# companion.net
KiCad netlist of a schematic drawn in EAGLE
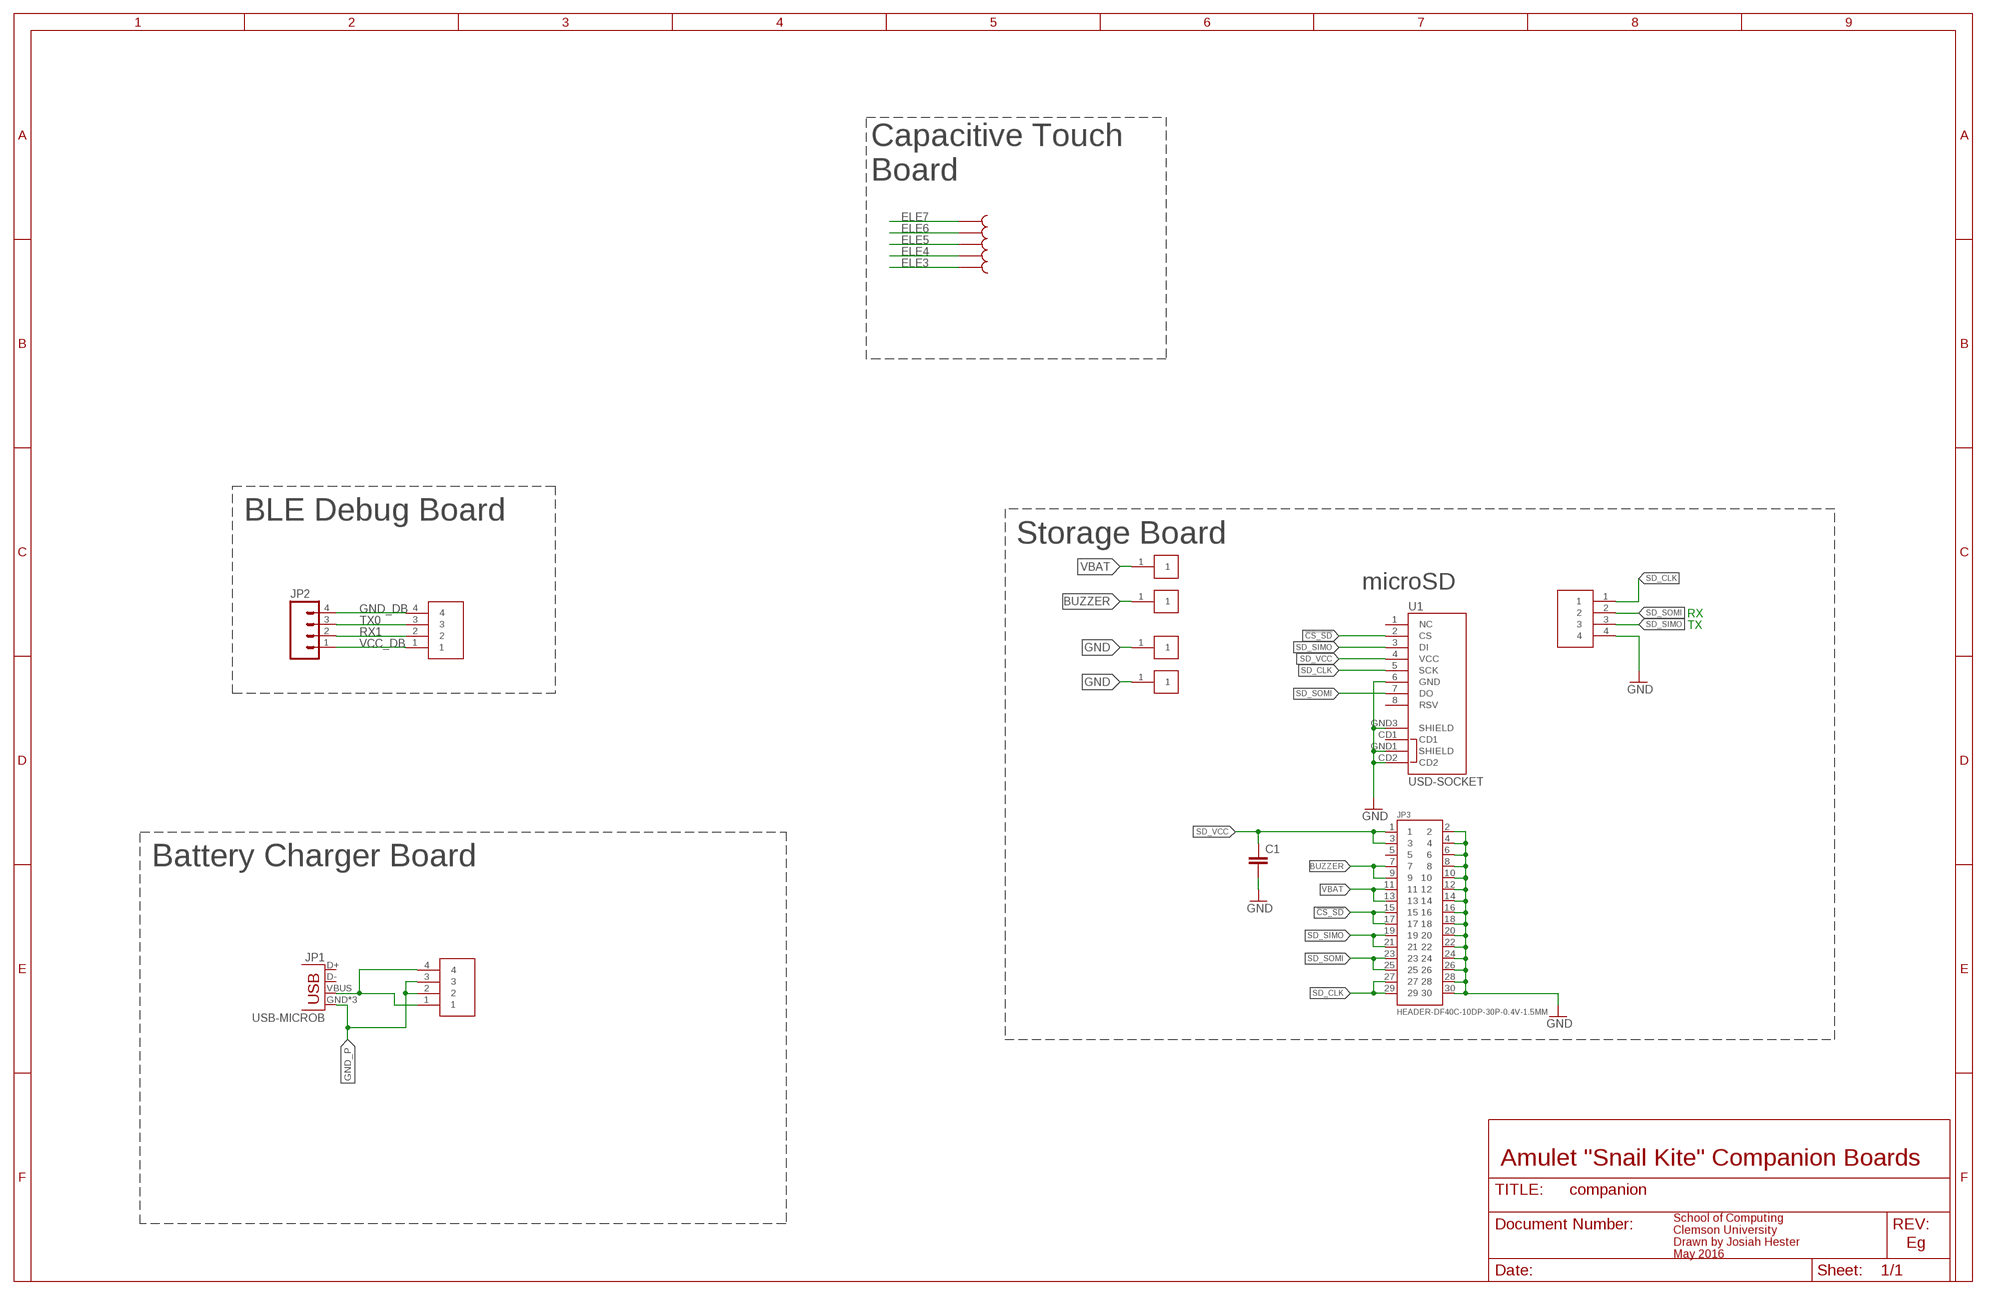
[diagram p0: schematic, sheet 1]

(export (version "E")
  (design (tool "Eeschema 10.0.6"))
  (components
    (comp (ref "C1")
      (value "CAP0805")
      (footprint "eagle-import:0805")
      (libsource (lib "eagle-import") (part "CAP0805"))
    )
    (comp (ref "JP1")
      (value "USB-MICROB")
      (footprint "eagle-import:USB-MICROB")
      (libsource (lib "eagle-import") (part "USB-MICROB"))
    )
    (comp (ref "JP2")
      (value "M04LOCK")
      (footprint "eagle-import:1X04_LOCK")
      (libsource (lib "eagle-import") (part "M04LOCK"))
    )
    (comp (ref "JP3")
      (value "HEADER-DF40C-10DP-30P-0.4V-1.5MM")
      (footprint "eagle-import:HEADER-DF40-30")
      (fields (field (name "DIGIKEY") "H11622CT-ND "))
      (libsource (lib "eagle-import") (part "HEADER-DF40C-10DP-30P-0.4V-1.5MM"))
    )
    (comp (ref "U$1")
      (value "CTPAD")
      (footprint "eagle-import:CTPAD")
      (libsource (lib "eagle-import") (part "CTPAD"))
    )
    (comp (ref "U$2")
      (value "CTPAD")
      (footprint "eagle-import:CTPAD")
      (libsource (lib "eagle-import") (part "CTPAD"))
    )
    (comp (ref "U$3")
      (value "CTPAD")
      (footprint "eagle-import:CTPAD")
      (libsource (lib "eagle-import") (part "CTPAD"))
    )
    (comp (ref "U$4")
      (value "CTPAD")
      (footprint "eagle-import:CTPAD")
      (libsource (lib "eagle-import") (part "CTPAD"))
    )
    (comp (ref "U$5")
      (value "CTPAD")
      (footprint "eagle-import:CTPAD")
      (libsource (lib "eagle-import") (part "CTPAD"))
    )
    (comp (ref "U$6")
      (value "1PAD")
      (footprint "eagle-import:5X23MM_PAD")
      (libsource (lib "eagle-import") (part "1PAD"))
    )
    (comp (ref "U$7")
      (value "1PAD")
      (footprint "eagle-import:5X23MM_PAD")
      (libsource (lib "eagle-import") (part "1PAD"))
    )
    (comp (ref "U$8")
      (value "1PAD")
      (footprint "eagle-import:5X23MM_PAD")
      (libsource (lib "eagle-import") (part "1PAD"))
    )
    (comp (ref "U$9")
      (value "1PAD")
      (footprint "eagle-import:5X23MM_PAD")
      (libsource (lib "eagle-import") (part "1PAD"))
    )
    (comp (ref "U$10")
      (value "1.27MM-MILLMAX")
      (footprint "eagle-import:1X03-1.27MM")
      (libsource (lib "eagle-import") (part "1.27MM-MILLMAX"))
    )
    (comp (ref "U$11")
      (value "1.27MM-MILLMAX")
      (footprint "eagle-import:1X03-1.27MM")
      (libsource (lib "eagle-import") (part "1.27MM-MILLMAX"))
    )
    (comp (ref "U$12")
      (value "1.27MM-MILLMAX")
      (footprint "eagle-import:1X03-1.27MM")
      (libsource (lib "eagle-import") (part "1.27MM-MILLMAX"))
    )
    (comp (ref "U1")
      (value "USD-SOCKET")
      (footprint "eagle-import:MICROSD_1_1")
      (libsource (lib "eagle-import") (part "USD-SOCKET"))
    )
  )
  (nets
    (net (code "1") (name "/ELE3") (class "Default")
      (node (ref "U$5") (pin "P$1") (pinfunction "P$1_P$1") (pintype "bidirectional"))
    )
    (net (code "2") (name "/ELE4") (class "Default")
      (node (ref "U$4") (pin "P$1") (pinfunction "P$1_P$1") (pintype "bidirectional"))
    )
    (net (code "3") (name "/ELE5") (class "Default")
      (node (ref "U$3") (pin "P$1") (pinfunction "P$1_P$1") (pintype "bidirectional"))
    )
    (net (code "4") (name "/ELE6") (class "Default")
      (node (ref "U$2") (pin "P$1") (pinfunction "P$1_P$1") (pintype "bidirectional"))
    )
    (net (code "5") (name "/ELE7") (class "Default")
      (node (ref "U$1") (pin "P$1") (pinfunction "P$1_P$1") (pintype "bidirectional"))
    )
    (net (code "6") (name "/GND_DB") (class "Default")
      (node (ref "JP2") (pin "4") (pinfunction "4_4") (pintype "passive"))
      (node (ref "U$12") (pin "4") (pinfunction "4_4") (pintype "bidirectional"))
    )
    (net (code "7") (name "/RX1") (class "Default")
      (node (ref "JP2") (pin "2") (pinfunction "2_2") (pintype "passive"))
      (node (ref "U$12") (pin "2") (pinfunction "2_2") (pintype "bidirectional"))
    )
    (net (code "8") (name "/TX0") (class "Default")
      (node (ref "JP2") (pin "3") (pinfunction "3_3") (pintype "passive"))
      (node (ref "U$12") (pin "3") (pinfunction "3_3") (pintype "bidirectional"))
    )
    (net (code "9") (name "/VCC_DB") (class "Default")
      (node (ref "JP2") (pin "1") (pinfunction "1_1") (pintype "passive"))
      (node (ref "U$12") (pin "1") (pinfunction "1_1") (pintype "bidirectional"))
    )
    (net (code "10") (name "/~{CS_SD}") (class "Default")
      (node (ref "JP3") (pin "15") (pinfunction "15_15") (pintype "bidirectional"))
      (node (ref "JP3") (pin "17") (pinfunction "17_17") (pintype "bidirectional"))
      (node (ref "U1") (pin "2") (pinfunction "CS_2") (pintype "bidirectional"))
    )
    (net (code "11") (name "BUZZER") (class "Default")
      (node (ref "JP3") (pin "7") (pinfunction "7_7") (pintype "bidirectional"))
      (node (ref "JP3") (pin "9") (pinfunction "9_9") (pintype "bidirectional"))
      (node (ref "U$7") (pin "1") (pinfunction "1_1") (pintype "bidirectional"))
    )
    (net (code "12") (name "GND") (class "Default")
      (node (ref "C1") (pin "2") (pinfunction "2_2") (pintype "passive"))
      (node (ref "JP3") (pin "10") (pinfunction "10_10") (pintype "bidirectional"))
      (node (ref "JP3") (pin "12") (pinfunction "12_12") (pintype "bidirectional"))
      (node (ref "JP3") (pin "14") (pinfunction "14_14") (pintype "bidirectional"))
      (node (ref "JP3") (pin "16") (pinfunction "16_16") (pintype "bidirectional"))
      (node (ref "JP3") (pin "18") (pinfunction "18_18") (pintype "bidirectional"))
      (node (ref "JP3") (pin "2") (pinfunction "2_2") (pintype "bidirectional"))
      (node (ref "JP3") (pin "20") (pinfunction "20_20") (pintype "bidirectional"))
      (node (ref "JP3") (pin "22") (pinfunction "22_22") (pintype "bidirectional"))
      (node (ref "JP3") (pin "24") (pinfunction "24_24") (pintype "bidirectional"))
      (node (ref "JP3") (pin "26") (pinfunction "26_26") (pintype "bidirectional"))
      (node (ref "JP3") (pin "28") (pinfunction "28_28") (pintype "bidirectional"))
      (node (ref "JP3") (pin "30") (pinfunction "30_30") (pintype "bidirectional"))
      (node (ref "JP3") (pin "4") (pinfunction "4_4") (pintype "bidirectional"))
      (node (ref "JP3") (pin "6") (pinfunction "6_6") (pintype "bidirectional"))
      (node (ref "JP3") (pin "8") (pinfunction "8_8") (pintype "bidirectional"))
      (node (ref "U$11") (pin "4") (pinfunction "4_4") (pintype "bidirectional"))
      (node (ref "U$8") (pin "1") (pinfunction "1_1") (pintype "bidirectional"))
      (node (ref "U$9") (pin "1") (pinfunction "1_1") (pintype "bidirectional"))
      (node (ref "U1") (pin "6") (pinfunction "GND_6") (pintype "bidirectional"))
      (node (ref "U1") (pin "CD2") (pinfunction "CD2_CD2") (pintype "bidirectional"))
      (node (ref "U1") (pin "GND1") (pinfunction "SHIELD_GND1") (pintype "bidirectional"))
      (node (ref "U1") (pin "GND3") (pinfunction "SHIELD_GND3") (pintype "bidirectional"))
    )
    (net (code "13") (name "GND_P") (class "Default")
      (node (ref "JP1") (pin "GND") (pinfunction "GND_GND") (pintype "bidirectional"))
      (node (ref "JP1") (pin "MT1") (pinfunction "GND_MT1") (pintype "bidirectional"))
      (node (ref "JP1") (pin "MT2") (pinfunction "GND_MT2") (pintype "bidirectional"))
      (node (ref "U$10") (pin "2") (pinfunction "2_2") (pintype "bidirectional"))
      (node (ref "U$10") (pin "3") (pinfunction "3_3") (pintype "bidirectional"))
    )
    (net (code "14") (name "Net-(JP1-PadVBUS)") (class "Default")
      (node (ref "JP1") (pin "VBUS") (pinfunction "VBUS_VBUS") (pintype "bidirectional"))
      (node (ref "U$10") (pin "1") (pinfunction "1_1") (pintype "bidirectional"))
      (node (ref "U$10") (pin "4") (pinfunction "4_4") (pintype "bidirectional"))
    )
    (net (code "15") (name "SD_CLK") (class "Default")
      (node (ref "JP3") (pin "27") (pinfunction "27_27") (pintype "bidirectional"))
      (node (ref "JP3") (pin "29") (pinfunction "29_29") (pintype "bidirectional"))
      (node (ref "U$11") (pin "1") (pinfunction "1_1") (pintype "bidirectional"))
      (node (ref "U1") (pin "5") (pinfunction "SCK_5") (pintype "bidirectional"))
    )
    (net (code "16") (name "SD_SIMO") (class "Default")
      (node (ref "JP3") (pin "19") (pinfunction "19_19") (pintype "bidirectional"))
      (node (ref "JP3") (pin "21") (pinfunction "21_21") (pintype "bidirectional"))
      (node (ref "U$11") (pin "3") (pinfunction "3_3") (pintype "bidirectional"))
      (node (ref "U1") (pin "3") (pinfunction "DI_3") (pintype "bidirectional"))
    )
    (net (code "17") (name "SD_SOMI") (class "Default")
      (node (ref "JP3") (pin "23") (pinfunction "23_23") (pintype "bidirectional"))
      (node (ref "JP3") (pin "25") (pinfunction "25_25") (pintype "bidirectional"))
      (node (ref "U$11") (pin "2") (pinfunction "2_2") (pintype "bidirectional"))
      (node (ref "U1") (pin "7") (pinfunction "DO_7") (pintype "bidirectional"))
    )
    (net (code "18") (name "SD_VCC") (class "Default")
      (node (ref "C1") (pin "1") (pinfunction "1_1") (pintype "passive"))
      (node (ref "JP3") (pin "1") (pinfunction "1_1") (pintype "bidirectional"))
      (node (ref "JP3") (pin "3") (pinfunction "3_3") (pintype "bidirectional"))
      (node (ref "U1") (pin "4") (pinfunction "VCC_4") (pintype "bidirectional"))
    )
    (net (code "19") (name "VBAT") (class "Default")
      (node (ref "JP3") (pin "11") (pinfunction "11_11") (pintype "bidirectional"))
      (node (ref "JP3") (pin "13") (pinfunction "13_13") (pintype "bidirectional"))
      (node (ref "U$6") (pin "1") (pinfunction "1_1") (pintype "bidirectional"))
    )
    (net (code "20") (name "unconnected-(JP1-PadD+)") (class "Default")
      (node (ref "JP1") (pin "D+") (pinfunction "D+_D+") (pintype "bidirectional"))
    )
    (net (code "21") (name "unconnected-(JP1-PadD-)") (class "Default")
      (node (ref "JP1") (pin "D-") (pinfunction "D-_D-") (pintype "bidirectional"))
    )
    (net (code "22") (name "unconnected-(JP3-Pad5)") (class "Default")
      (node (ref "JP3") (pin "5") (pinfunction "5_5") (pintype "bidirectional"))
    )
    (net (code "23") (name "unconnected-(U1-NC-Pad1)") (class "Default")
      (node (ref "U1") (pin "1") (pinfunction "NC_1") (pintype "bidirectional"))
    )
    (net (code "24") (name "unconnected-(U1-PadCD1)") (class "Default")
      (node (ref "U1") (pin "CD1") (pinfunction "CD1_CD1") (pintype "bidirectional"))
    )
    (net (code "25") (name "unconnected-(U1-RSV-Pad8)") (class "Default")
      (node (ref "U1") (pin "8") (pinfunction "RSV_8") (pintype "bidirectional"))
    )
  )
)
